# AD.net
KiCad netlist of a schematic drawn in Altium Designer
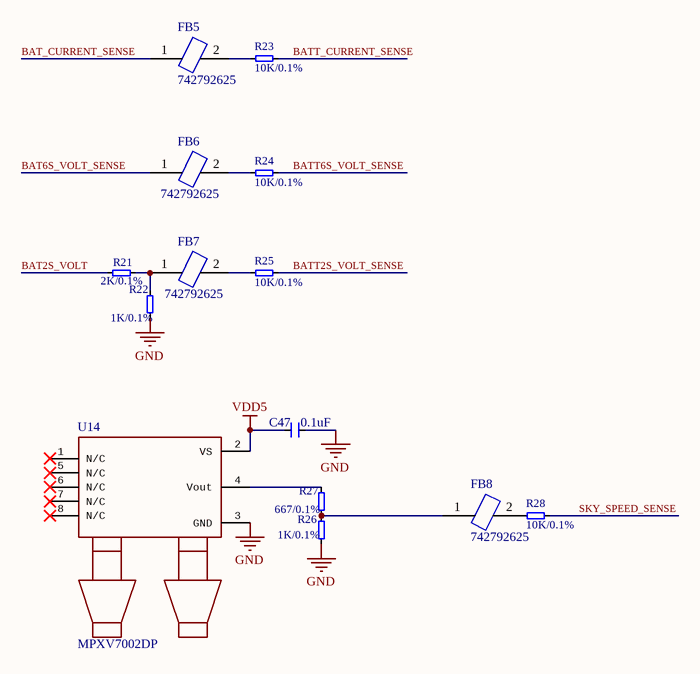
[diagram p0: AD.SchDoc]

(export (version "E")
  (design (tool "Eeschema 10.0.6"))
  (components
    (comp (ref "C47") (value "0.1uF") (footprint "0603C") (libsource (lib "研发中心原理图库文件") (part "C")))
    (comp (ref "FB5")
      (value "742792625")
      (footprint "研发中心PCB库文件:0603-FB")
      (libsource (lib "研发中心原理图库文件") (part "FB"))
    )
    (comp (ref "FB6")
      (value "742792625")
      (footprint "研发中心PCB库文件:0603-FB")
      (libsource (lib "研发中心原理图库文件") (part "FB"))
    )
    (comp (ref "FB7")
      (value "742792625")
      (footprint "研发中心PCB库文件:0603-FB")
      (libsource (lib "研发中心原理图库文件") (part "FB"))
    )
    (comp (ref "FB8")
      (value "742792625")
      (footprint "研发中心PCB库文件:0603-FB")
      (libsource (lib "研发中心原理图库文件") (part "FB"))
    )
    (comp (ref "R21") (value "2K/0.1%") (footprint "0603R") (libsource (lib "研发中心原理图库文件") (part "R")))
    (comp (ref "R22") (value "1K/0.1%") (footprint "0603R") (libsource (lib "研发中心原理图库文件") (part "R")))
    (comp (ref "R23") (value "10K/0.1%") (footprint "0603R") (libsource (lib "研发中心原理图库文件") (part "R")))
    (comp (ref "R24") (value "10K/0.1%") (footprint "0603R") (libsource (lib "研发中心原理图库文件") (part "R")))
    (comp (ref "R25") (value "10K/0.1%") (footprint "0603R") (libsource (lib "研发中心原理图库文件") (part "R")))
    (comp (ref "R26") (value "1K/0.1%") (footprint "0603R") (libsource (lib "研发中心原理图库文件") (part "R")))
    (comp (ref "R27") (value "667/0.1%") (footprint "0603R") (libsource (lib "研发中心原理图库文件") (part "R")))
    (comp (ref "R28") (value "10K/0.1%") (footprint "0603R") (libsource (lib "研发中心原理图库文件") (part "R")))
    (comp (ref "U14")
      (value "MPXV7002DP")
      (footprint "MPXV7002DP")
      (libsource (lib "研发中心原理图库文件") (part "MPXV7002DP"))
    )
  )
  (nets
    (net (code "1") (name "/BAT2S_VOLT") (class "Default") (node (ref "R21") (pin "1") (pintype "passive")))
    (net (code "2") (name "/BAT6S_VOLT_SENSE") (class "Default")
      (node (ref "FB6") (pin "1") (pinfunction "1_1") (pintype "passive"))
    )
    (net (code "3") (name "/BATT2S_VOLT_SENSE") (class "Default")
      (node (ref "R25") (pin "1") (pintype "passive"))
    )
    (net (code "4") (name "/BATT6S_VOLT_SENSE") (class "Default")
      (node (ref "R24") (pin "1") (pintype "passive"))
    )
    (net (code "5") (name "/BATT_CURRENT_SENSE") (class "Default")
      (node (ref "R23") (pin "1") (pintype "passive"))
    )
    (net (code "6") (name "/BAT_CURRENT_SENSE") (class "Default")
      (node (ref "FB5") (pin "1") (pinfunction "1_1") (pintype "passive"))
    )
    (net (code "7") (name "/SKY_SPEED_SENSE") (class "Default")
      (node (ref "R28") (pin "1") (pintype "passive"))
    )
    (net (code "8") (name "GND") (class "Default")
      (node (ref "C47") (pin "1") (pintype "passive"))
      (node (ref "R22") (pin "2") (pintype "passive"))
      (node (ref "R26") (pin "1") (pintype "passive"))
      (node (ref "U14") (pin "3") (pinfunction "GND_3") (pintype "passive"))
    )
    (net (code "9") (name "Net-(FB5-Pad2)") (class "Default")
      (node (ref "FB5") (pin "2") (pinfunction "2_2") (pintype "passive"))
      (node (ref "R23") (pin "2") (pintype "passive"))
    )
    (net (code "10") (name "Net-(FB6-Pad2)") (class "Default")
      (node (ref "FB6") (pin "2") (pinfunction "2_2") (pintype "passive"))
      (node (ref "R24") (pin "2") (pintype "passive"))
    )
    (net (code "11") (name "Net-(FB7-Pad1)") (class "Default")
      (node (ref "FB7") (pin "1") (pinfunction "1_1") (pintype "passive"))
      (node (ref "R21") (pin "2") (pintype "passive"))
      (node (ref "R22") (pin "1") (pintype "passive"))
    )
    (net (code "12") (name "Net-(FB7-Pad2)") (class "Default")
      (node (ref "FB7") (pin "2") (pinfunction "2_2") (pintype "passive"))
      (node (ref "R25") (pin "2") (pintype "passive"))
    )
    (net (code "13") (name "Net-(FB8-Pad1)") (class "Default")
      (node (ref "FB8") (pin "1") (pinfunction "1_1") (pintype "passive"))
      (node (ref "R26") (pin "2") (pintype "passive"))
      (node (ref "R27") (pin "1") (pintype "passive"))
    )
    (net (code "14") (name "Net-(FB8-Pad2)") (class "Default")
      (node (ref "FB8") (pin "2") (pinfunction "2_2") (pintype "passive"))
      (node (ref "R28") (pin "2") (pintype "passive"))
    )
    (net (code "15") (name "Net-(U14-Vout)") (class "Default")
      (node (ref "R27") (pin "2") (pintype "passive"))
      (node (ref "U14") (pin "4") (pinfunction "Vout_4") (pintype "passive"))
    )
    (net (code "16") (name "VDD5") (class "Default")
      (node (ref "C47") (pin "2") (pintype "passive"))
      (node (ref "U14") (pin "2") (pinfunction "VS_2") (pintype "passive"))
    )
    (net (code "17") (name "unconnected-(U14-N{slash}C-Pad1)") (class "Default")
      (node (ref "U14") (pin "1") (pinfunction "N/C_1") (pintype "passive+no_connect"))
    )
    (net (code "18") (name "unconnected-(U14-N{slash}C-Pad5)") (class "Default")
      (node (ref "U14") (pin "5") (pinfunction "N/C_5") (pintype "passive+no_connect"))
    )
    (net (code "19") (name "unconnected-(U14-N{slash}C-Pad6)") (class "Default")
      (node (ref "U14") (pin "6") (pinfunction "N/C_6") (pintype "passive+no_connect"))
    )
    (net (code "20") (name "unconnected-(U14-N{slash}C-Pad7)") (class "Default")
      (node (ref "U14") (pin "7") (pinfunction "N/C_7") (pintype "passive+no_connect"))
    )
    (net (code "21") (name "unconnected-(U14-N{slash}C-Pad8)") (class "Default")
      (node (ref "U14") (pin "8") (pinfunction "N/C_8") (pintype "passive+no_connect"))
    )
  )
)
